# AVRI2CIO_V0_3_LEVEL1.net
KiCad netlist of a schematic drawn in EAGLE
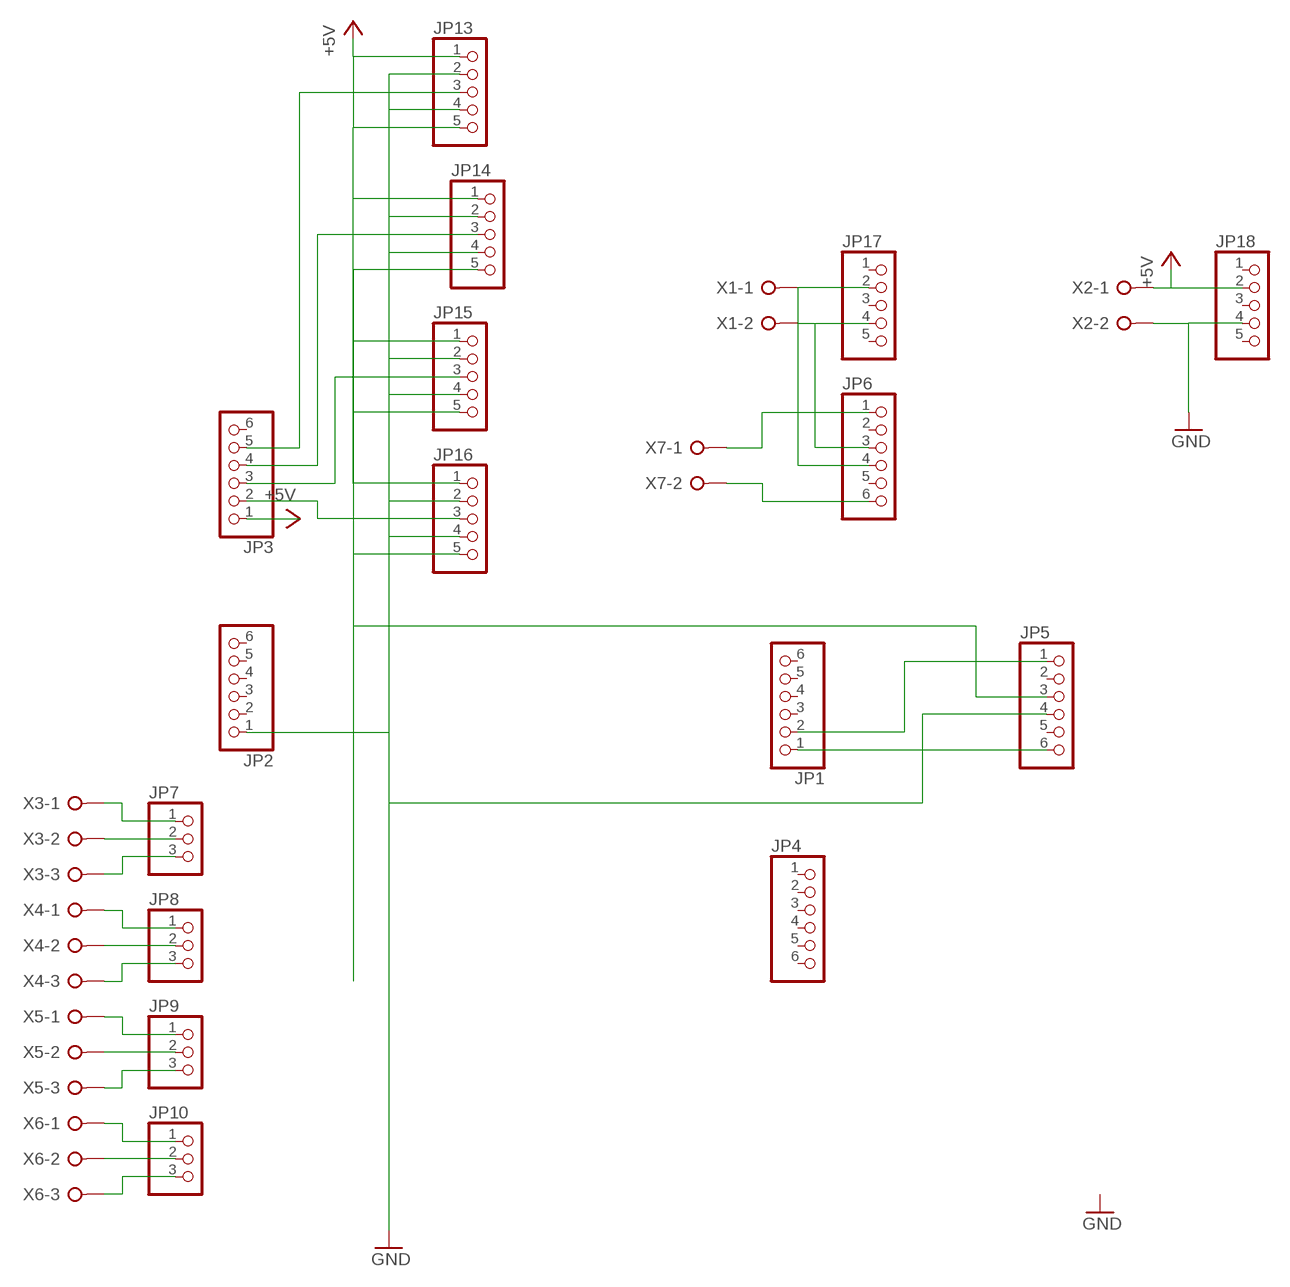
[diagram p0: schematic, sheet 1]

(export (version "E")
  (design (tool "Eeschema 10.0.6"))
  (components
    (comp (ref "JP1")
      (value "PINHD-1X6")
      (footprint "eagle-import:1X06")
      (libsource (lib "eagle-import") (part "PINHD-1X6"))
    )
    (comp (ref "JP2")
      (value "PINHD-1X6")
      (footprint "eagle-import:1X06")
      (libsource (lib "eagle-import") (part "PINHD-1X6"))
    )
    (comp (ref "JP3")
      (value "PINHD-1X6")
      (footprint "eagle-import:1X06")
      (libsource (lib "eagle-import") (part "PINHD-1X6"))
    )
    (comp (ref "JP4")
      (value "PINHD-1X6")
      (footprint "eagle-import:1X06")
      (libsource (lib "eagle-import") (part "PINHD-1X6"))
    )
    (comp (ref "JP5")
      (value "PINHD-1X6")
      (footprint "eagle-import:1X06")
      (libsource (lib "eagle-import") (part "PINHD-1X6"))
    )
    (comp (ref "JP6")
      (value "PINHD-1X6")
      (footprint "eagle-import:1X06")
      (libsource (lib "eagle-import") (part "PINHD-1X6"))
    )
    (comp (ref "JP7")
      (value "PINHD-1X3")
      (footprint "eagle-import:1X03")
      (libsource (lib "eagle-import") (part "PINHD-1X3"))
    )
    (comp (ref "JP8")
      (value "PINHD-1X3")
      (footprint "eagle-import:1X03")
      (libsource (lib "eagle-import") (part "PINHD-1X3"))
    )
    (comp (ref "JP9")
      (value "PINHD-1X3")
      (footprint "eagle-import:1X03")
      (libsource (lib "eagle-import") (part "PINHD-1X3"))
    )
    (comp (ref "JP10")
      (value "PINHD-1X3")
      (footprint "eagle-import:1X03")
      (libsource (lib "eagle-import") (part "PINHD-1X3"))
    )
    (comp (ref "JP13")
      (value "PINHD-1X5")
      (footprint "eagle-import:1X05")
      (libsource (lib "eagle-import") (part "PINHD-1X5"))
    )
    (comp (ref "JP14")
      (value "PINHD-1X5")
      (footprint "eagle-import:1X05")
      (libsource (lib "eagle-import") (part "PINHD-1X5"))
    )
    (comp (ref "JP15")
      (value "PINHD-1X5")
      (footprint "eagle-import:1X05")
      (libsource (lib "eagle-import") (part "PINHD-1X5"))
    )
    (comp (ref "JP16")
      (value "PINHD-1X5")
      (footprint "eagle-import:1X05")
      (libsource (lib "eagle-import") (part "PINHD-1X5"))
    )
    (comp (ref "JP17")
      (value "PINHD-1X5")
      (footprint "eagle-import:1X05")
      (libsource (lib "eagle-import") (part "PINHD-1X5"))
    )
    (comp (ref "JP18")
      (value "PINHD-1X5")
      (footprint "eagle-import:1X05")
      (libsource (lib "eagle-import") (part "PINHD-1X5"))
    )
    (comp (ref "X1")
      (value "W237-02P")
      (footprint "eagle-import:W237-132")
      (libsource (lib "eagle-import") (part "W237-02P"))
    )
    (comp (ref "X2")
      (value "W237-02P")
      (footprint "eagle-import:W237-132")
      (libsource (lib "eagle-import") (part "W237-02P"))
    )
    (comp (ref "X3")
      (value "W237-3E")
      (footprint "eagle-import:W237-3E")
      (libsource (lib "eagle-import") (part "W237-3E"))
    )
    (comp (ref "X4")
      (value "W237-3E")
      (footprint "eagle-import:W237-3E")
      (libsource (lib "eagle-import") (part "W237-3E"))
    )
    (comp (ref "X5")
      (value "W237-3E")
      (footprint "eagle-import:W237-3E")
      (libsource (lib "eagle-import") (part "W237-3E"))
    )
    (comp (ref "X6")
      (value "W237-3E")
      (footprint "eagle-import:W237-3E")
      (libsource (lib "eagle-import") (part "W237-3E"))
    )
    (comp (ref "X7")
      (value "W237-02P")
      (footprint "eagle-import:W237-132")
      (libsource (lib "eagle-import") (part "W237-02P"))
    )
  )
  (nets
    (net (code "1") (name "+5V") (class "Default")
      (node (ref "JP13") (pin "1") (pinfunction "1_1") (pintype "passive"))
      (node (ref "JP13") (pin "5") (pinfunction "5_5") (pintype "passive"))
      (node (ref "JP14") (pin "1") (pinfunction "1_1") (pintype "passive"))
      (node (ref "JP14") (pin "5") (pinfunction "5_5") (pintype "passive"))
      (node (ref "JP15") (pin "1") (pinfunction "1_1") (pintype "passive"))
      (node (ref "JP15") (pin "5") (pinfunction "5_5") (pintype "passive"))
      (node (ref "JP16") (pin "1") (pinfunction "1_1") (pintype "passive"))
      (node (ref "JP16") (pin "5") (pinfunction "5_5") (pintype "passive"))
      (node (ref "JP18") (pin "2") (pinfunction "2_2") (pintype "passive"))
      (node (ref "JP3") (pin "1") (pinfunction "1_1") (pintype "passive"))
      (node (ref "JP5") (pin "3") (pinfunction "3_3") (pintype "passive"))
      (node (ref "X2") (pin "1") (pinfunction "KL_1") (pintype "passive"))
    )
    (net (code "2") (name "GND") (class "Default")
      (node (ref "JP13") (pin "2") (pinfunction "2_2") (pintype "passive"))
      (node (ref "JP13") (pin "4") (pinfunction "4_4") (pintype "passive"))
      (node (ref "JP14") (pin "2") (pinfunction "2_2") (pintype "passive"))
      (node (ref "JP14") (pin "4") (pinfunction "4_4") (pintype "passive"))
      (node (ref "JP15") (pin "2") (pinfunction "2_2") (pintype "passive"))
      (node (ref "JP15") (pin "4") (pinfunction "4_4") (pintype "passive"))
      (node (ref "JP16") (pin "2") (pinfunction "2_2") (pintype "passive"))
      (node (ref "JP16") (pin "4") (pinfunction "4_4") (pintype "passive"))
      (node (ref "JP18") (pin "4") (pinfunction "4_4") (pintype "passive"))
      (node (ref "JP2") (pin "1") (pinfunction "1_1") (pintype "passive"))
      (node (ref "JP5") (pin "4") (pinfunction "4_4") (pintype "passive"))
      (node (ref "X2") (pin "2") (pinfunction "KL_2") (pintype "passive"))
    )
    (net (code "3") (name "Net-(JP1-Pad1)") (class "Default")
      (node (ref "JP1") (pin "1") (pinfunction "1_1") (pintype "passive"))
      (node (ref "JP5") (pin "6") (pinfunction "6_6") (pintype "passive"))
    )
    (net (code "4") (name "Net-(JP1-Pad2)") (class "Default")
      (node (ref "JP1") (pin "2") (pinfunction "2_2") (pintype "passive"))
      (node (ref "JP5") (pin "1") (pinfunction "1_1") (pintype "passive"))
    )
    (net (code "5") (name "Net-(JP13-Pad3)") (class "Default")
      (node (ref "JP13") (pin "3") (pinfunction "3_3") (pintype "passive"))
      (node (ref "JP3") (pin "5") (pinfunction "5_5") (pintype "passive"))
    )
    (net (code "6") (name "Net-(JP14-Pad3)") (class "Default")
      (node (ref "JP14") (pin "3") (pinfunction "3_3") (pintype "passive"))
      (node (ref "JP3") (pin "4") (pinfunction "4_4") (pintype "passive"))
    )
    (net (code "7") (name "Net-(JP15-Pad3)") (class "Default")
      (node (ref "JP15") (pin "3") (pinfunction "3_3") (pintype "passive"))
      (node (ref "JP3") (pin "3") (pinfunction "3_3") (pintype "passive"))
    )
    (net (code "8") (name "Net-(JP16-Pad3)") (class "Default")
      (node (ref "JP16") (pin "3") (pinfunction "3_3") (pintype "passive"))
      (node (ref "JP3") (pin "2") (pinfunction "2_2") (pintype "passive"))
    )
    (net (code "9") (name "Net-(X1A-KL)") (class "Default")
      (node (ref "JP17") (pin "2") (pinfunction "2_2") (pintype "passive"))
      (node (ref "JP6") (pin "4") (pinfunction "4_4") (pintype "passive"))
      (node (ref "X1") (pin "1") (pinfunction "KL_1") (pintype "passive"))
    )
    (net (code "10") (name "Net-(X1B-KL)") (class "Default")
      (node (ref "JP17") (pin "4") (pinfunction "4_4") (pintype "passive"))
      (node (ref "JP6") (pin "3") (pinfunction "3_3") (pintype "passive"))
      (node (ref "X1") (pin "2") (pinfunction "KL_2") (pintype "passive"))
    )
    (net (code "11") (name "Net-(X3A-KL)") (class "Default")
      (node (ref "JP7") (pin "1") (pinfunction "1_1") (pintype "passive"))
      (node (ref "X3") (pin "1") (pinfunction "KL_1") (pintype "passive"))
    )
    (net (code "12") (name "Net-(X3B-KL)") (class "Default")
      (node (ref "JP7") (pin "2") (pinfunction "2_2") (pintype "passive"))
      (node (ref "X3") (pin "2") (pinfunction "KL_2") (pintype "passive"))
    )
    (net (code "13") (name "Net-(X3C-KL)") (class "Default")
      (node (ref "JP7") (pin "3") (pinfunction "3_3") (pintype "passive"))
      (node (ref "X3") (pin "3") (pinfunction "KL_3") (pintype "passive"))
    )
    (net (code "14") (name "Net-(X4A-KL)") (class "Default")
      (node (ref "JP8") (pin "1") (pinfunction "1_1") (pintype "passive"))
      (node (ref "X4") (pin "1") (pinfunction "KL_1") (pintype "passive"))
    )
    (net (code "15") (name "Net-(X4B-KL)") (class "Default")
      (node (ref "JP8") (pin "2") (pinfunction "2_2") (pintype "passive"))
      (node (ref "X4") (pin "2") (pinfunction "KL_2") (pintype "passive"))
    )
    (net (code "16") (name "Net-(X4C-KL)") (class "Default")
      (node (ref "JP8") (pin "3") (pinfunction "3_3") (pintype "passive"))
      (node (ref "X4") (pin "3") (pinfunction "KL_3") (pintype "passive"))
    )
    (net (code "17") (name "Net-(X5A-KL)") (class "Default")
      (node (ref "JP9") (pin "1") (pinfunction "1_1") (pintype "passive"))
      (node (ref "X5") (pin "1") (pinfunction "KL_1") (pintype "passive"))
    )
    (net (code "18") (name "Net-(X5B-KL)") (class "Default")
      (node (ref "JP9") (pin "2") (pinfunction "2_2") (pintype "passive"))
      (node (ref "X5") (pin "2") (pinfunction "KL_2") (pintype "passive"))
    )
    (net (code "19") (name "Net-(X5C-KL)") (class "Default")
      (node (ref "JP9") (pin "3") (pinfunction "3_3") (pintype "passive"))
      (node (ref "X5") (pin "3") (pinfunction "KL_3") (pintype "passive"))
    )
    (net (code "20") (name "Net-(X6A-KL)") (class "Default")
      (node (ref "JP10") (pin "1") (pinfunction "1_1") (pintype "passive"))
      (node (ref "X6") (pin "1") (pinfunction "KL_1") (pintype "passive"))
    )
    (net (code "21") (name "Net-(X6B-KL)") (class "Default")
      (node (ref "JP10") (pin "2") (pinfunction "2_2") (pintype "passive"))
      (node (ref "X6") (pin "2") (pinfunction "KL_2") (pintype "passive"))
    )
    (net (code "22") (name "Net-(X6C-KL)") (class "Default")
      (node (ref "JP10") (pin "3") (pinfunction "3_3") (pintype "passive"))
      (node (ref "X6") (pin "3") (pinfunction "KL_3") (pintype "passive"))
    )
    (net (code "23") (name "Net-(X7A-KL)") (class "Default")
      (node (ref "JP6") (pin "1") (pinfunction "1_1") (pintype "passive"))
      (node (ref "X7") (pin "1") (pinfunction "KL_1") (pintype "passive"))
    )
    (net (code "24") (name "Net-(X7B-KL)") (class "Default")
      (node (ref "JP6") (pin "6") (pinfunction "6_6") (pintype "passive"))
      (node (ref "X7") (pin "2") (pinfunction "KL_2") (pintype "passive"))
    )
    (net (code "25") (name "unconnected-(JP1-Pad3)") (class "Default")
      (node (ref "JP1") (pin "3") (pinfunction "3_3") (pintype "passive"))
    )
    (net (code "26") (name "unconnected-(JP1-Pad4)") (class "Default")
      (node (ref "JP1") (pin "4") (pinfunction "4_4") (pintype "passive"))
    )
    (net (code "27") (name "unconnected-(JP1-Pad5)") (class "Default")
      (node (ref "JP1") (pin "5") (pinfunction "5_5") (pintype "passive"))
    )
    (net (code "28") (name "unconnected-(JP1-Pad6)") (class "Default")
      (node (ref "JP1") (pin "6") (pinfunction "6_6") (pintype "passive"))
    )
    (net (code "29") (name "unconnected-(JP2-Pad2)") (class "Default")
      (node (ref "JP2") (pin "2") (pinfunction "2_2") (pintype "passive"))
    )
    (net (code "30") (name "unconnected-(JP2-Pad3)") (class "Default")
      (node (ref "JP2") (pin "3") (pinfunction "3_3") (pintype "passive"))
    )
    (net (code "31") (name "unconnected-(JP2-Pad4)") (class "Default")
      (node (ref "JP2") (pin "4") (pinfunction "4_4") (pintype "passive"))
    )
    (net (code "32") (name "unconnected-(JP2-Pad5)") (class "Default")
      (node (ref "JP2") (pin "5") (pinfunction "5_5") (pintype "passive"))
    )
    (net (code "33") (name "unconnected-(JP2-Pad6)") (class "Default")
      (node (ref "JP2") (pin "6") (pinfunction "6_6") (pintype "passive"))
    )
    (net (code "34") (name "unconnected-(JP3-Pad6)") (class "Default")
      (node (ref "JP3") (pin "6") (pinfunction "6_6") (pintype "passive"))
    )
    (net (code "35") (name "unconnected-(JP4-Pad1)") (class "Default")
      (node (ref "JP4") (pin "1") (pinfunction "1_1") (pintype "passive"))
    )
    (net (code "36") (name "unconnected-(JP4-Pad2)") (class "Default")
      (node (ref "JP4") (pin "2") (pinfunction "2_2") (pintype "passive"))
    )
    (net (code "37") (name "unconnected-(JP4-Pad3)") (class "Default")
      (node (ref "JP4") (pin "3") (pinfunction "3_3") (pintype "passive"))
    )
    (net (code "38") (name "unconnected-(JP4-Pad4)") (class "Default")
      (node (ref "JP4") (pin "4") (pinfunction "4_4") (pintype "passive"))
    )
    (net (code "39") (name "unconnected-(JP4-Pad5)") (class "Default")
      (node (ref "JP4") (pin "5") (pinfunction "5_5") (pintype "passive"))
    )
    (net (code "40") (name "unconnected-(JP4-Pad6)") (class "Default")
      (node (ref "JP4") (pin "6") (pinfunction "6_6") (pintype "passive"))
    )
    (net (code "41") (name "unconnected-(JP5-Pad2)") (class "Default")
      (node (ref "JP5") (pin "2") (pinfunction "2_2") (pintype "passive"))
    )
    (net (code "42") (name "unconnected-(JP5-Pad5)") (class "Default")
      (node (ref "JP5") (pin "5") (pinfunction "5_5") (pintype "passive"))
    )
    (net (code "43") (name "unconnected-(JP6-Pad2)") (class "Default")
      (node (ref "JP6") (pin "2") (pinfunction "2_2") (pintype "passive"))
    )
    (net (code "44") (name "unconnected-(JP6-Pad5)") (class "Default")
      (node (ref "JP6") (pin "5") (pinfunction "5_5") (pintype "passive"))
    )
    (net (code "45") (name "unconnected-(JP17-Pad1)") (class "Default")
      (node (ref "JP17") (pin "1") (pinfunction "1_1") (pintype "passive"))
    )
    (net (code "46") (name "unconnected-(JP17-Pad3)") (class "Default")
      (node (ref "JP17") (pin "3") (pinfunction "3_3") (pintype "passive"))
    )
    (net (code "47") (name "unconnected-(JP17-Pad5)") (class "Default")
      (node (ref "JP17") (pin "5") (pinfunction "5_5") (pintype "passive"))
    )
    (net (code "48") (name "unconnected-(JP18-Pad1)") (class "Default")
      (node (ref "JP18") (pin "1") (pinfunction "1_1") (pintype "passive"))
    )
    (net (code "49") (name "unconnected-(JP18-Pad3)") (class "Default")
      (node (ref "JP18") (pin "3") (pinfunction "3_3") (pintype "passive"))
    )
    (net (code "50") (name "unconnected-(JP18-Pad5)") (class "Default")
      (node (ref "JP18") (pin "5") (pinfunction "5_5") (pintype "passive"))
    )
  )
)
